# SCH_Cansat_PCB_Flight_Computer_Only_2026.net
KiCad netlist of a schematic drawn in EasyEDA
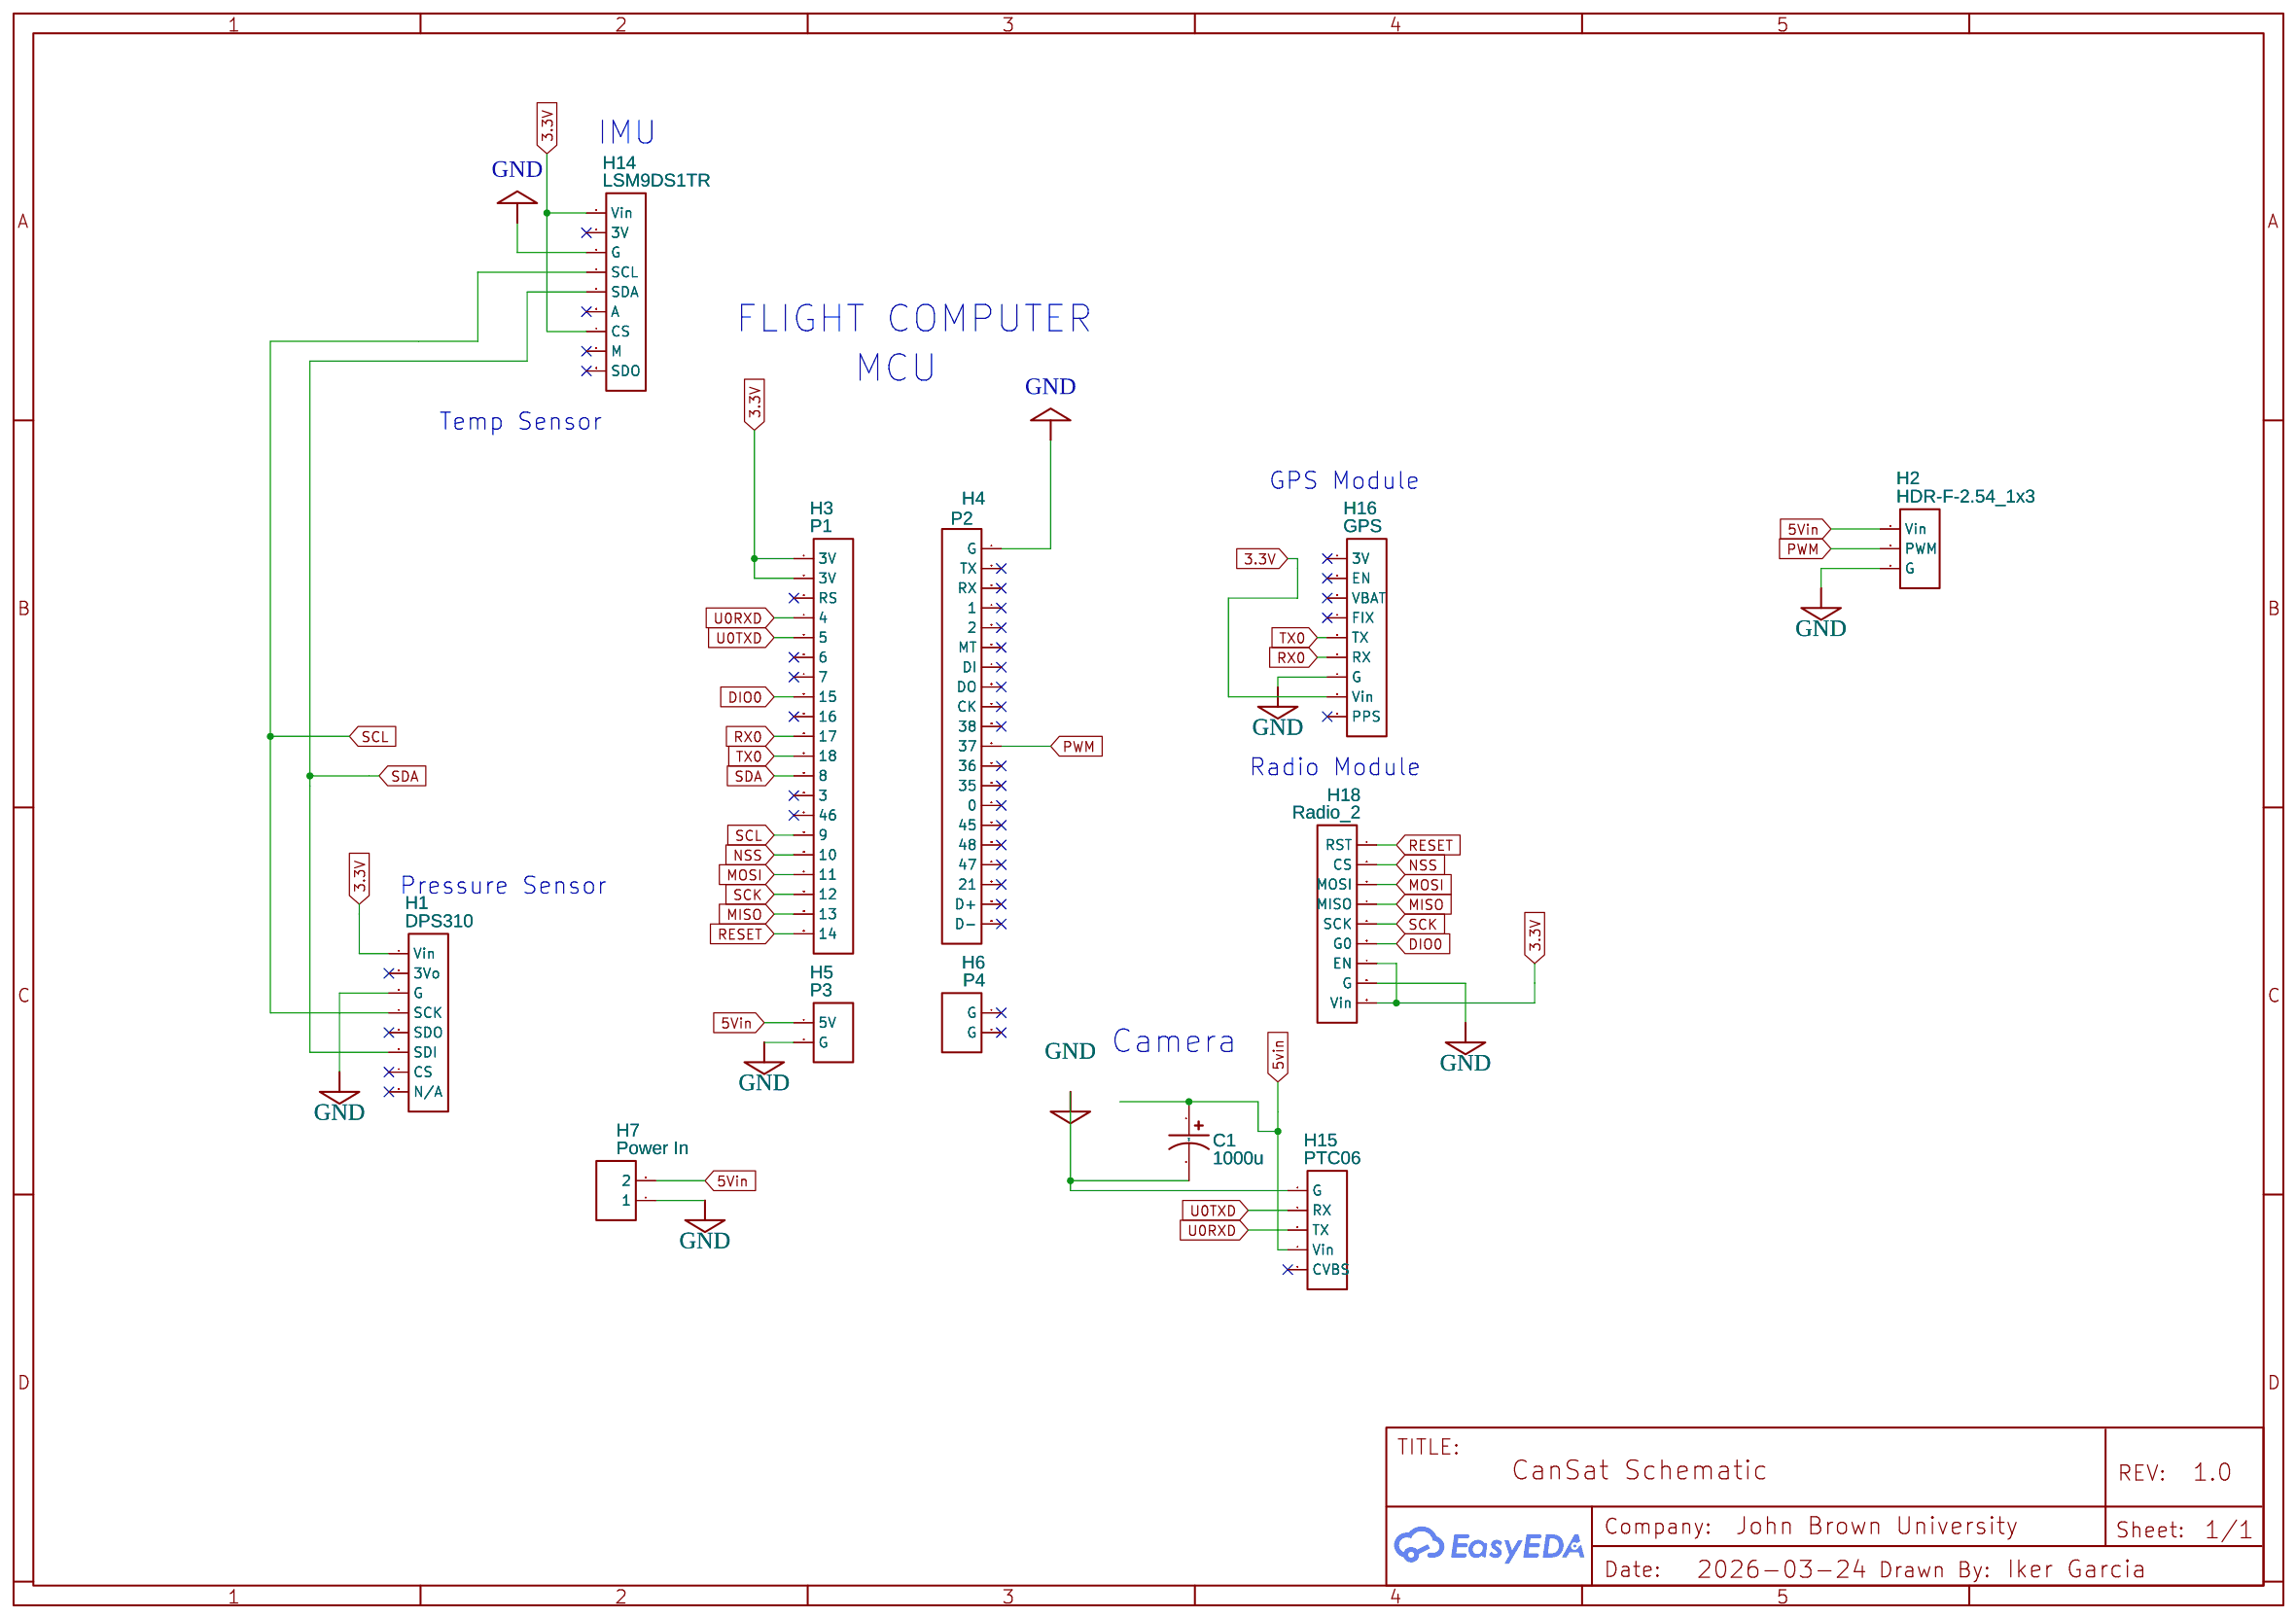
[diagram p0: schematic sheet]

(export (version "E")
  (design (tool "Eeschema 10.0.6"))
  (components
    (comp (ref "C1") (value "1000u") (libsource (lib "") (part "CE_TH_D6.3×F2.5_US")))
    (comp (ref "H1") (value "DPS310") (libsource (lib "") (part "HDR-F-2.54_1x8")))
    (comp (ref "H2") (value "HDR-F-2.54_1x3") (libsource (lib "") (part "HDR-F-2.54_1x3")))
    (comp (ref "H3") (value "P1") (libsource (lib "") (part "HDR-F-2.54_1x20")))
    (comp (ref "H4") (value "P2") (libsource (lib "") (part "HDR-F-2.54_1x20_1")))
    (comp (ref "H5") (value "P3") (libsource (lib "") (part "HDR-F-2.54_1x2_1")))
    (comp (ref "H6") (value "P4") (libsource (lib "") (part "HDR-F-2.54_1x2")))
    (comp (ref "H7") (value "Power In") (libsource (lib "") (part "HDR-F-2.54_1x2_2")))
    (comp (ref "H14") (value "LSM9DS1TR") (libsource (lib "") (part "HDR-F-2.54_1x9_2")))
    (comp (ref "H15") (value "PTC06") (libsource (lib "") (part "HDR-F-2.54_1x5")))
    (comp (ref "H16") (value "GPS") (libsource (lib "") (part "HDR-F-2.54_1x9_1")))
    (comp (ref "H18") (value "Radio_2") (libsource (lib "") (part "HDR-F-2.54_1x9")))
  )
  (nets
    (net (code "1") (name "3.3V") (class "Default")
      (node (ref "H1") (pin "1") (pinfunction "Vin_1") (pintype "unspecified"))
      (node (ref "H14") (pin "1") (pinfunction "Vin_1") (pintype "unspecified"))
      (node (ref "H14") (pin "7") (pinfunction "CS_7") (pintype "unspecified"))
      (node (ref "H16") (pin "8") (pinfunction "Vin_8") (pintype "unspecified"))
      (node (ref "H18") (pin "7") (pinfunction "EN_7") (pintype "unspecified"))
      (node (ref "H18") (pin "9") (pinfunction "Vin_9") (pintype "unspecified"))
      (node (ref "H3") (pin "1") (pinfunction "3V_1") (pintype "unspecified"))
      (node (ref "H3") (pin "2") (pinfunction "3V_2") (pintype "unspecified"))
    )
    (net (code "2") (name "5Vin") (class "Default")
      (node (ref "H2") (pin "1") (pinfunction "Vin_1") (pintype "input"))
      (node (ref "H5") (pin "1") (pinfunction "5V_1") (pintype "input"))
      (node (ref "H7") (pin "2") (pinfunction "2_2") (pintype "input"))
    )
    (net (code "3") (name "5vin") (class "Default")
      (node (ref "C1") (pin "1") (pinfunction "1_1") (pintype "unspecified"))
      (node (ref "H15") (pin "4") (pinfunction "Vin_4") (pintype "unspecified"))
    )
    (net (code "4") (name "DIO0") (class "Default")
      (node (ref "H18") (pin "6") (pinfunction "G0_6") (pintype "unspecified"))
      (node (ref "H3") (pin "8") (pinfunction "15_8") (pintype "unspecified"))
    )
    (net (code "5") (name "GND") (class "Default")
      (node (ref "C1") (pin "2") (pinfunction "2_2") (pintype "unspecified"))
      (node (ref "H1") (pin "3") (pinfunction "G_3") (pintype "unspecified"))
      (node (ref "H14") (pin "3") (pinfunction "G_3") (pintype "unspecified"))
      (node (ref "H15") (pin "1") (pinfunction "G_1") (pintype "unspecified"))
      (node (ref "H16") (pin "7") (pinfunction "G_7") (pintype "unspecified"))
      (node (ref "H18") (pin "8") (pinfunction "G_8") (pintype "unspecified"))
      (node (ref "H2") (pin "3") (pinfunction "G_3") (pintype "input"))
      (node (ref "H4") (pin "1") (pinfunction "G_1") (pintype "unspecified"))
      (node (ref "H5") (pin "2") (pinfunction "G_2") (pintype "input"))
      (node (ref "H7") (pin "1") (pinfunction "1_1") (pintype "input"))
    )
    (net (code "6") (name "MISO") (class "Default")
      (node (ref "H18") (pin "4") (pinfunction "MISO_4") (pintype "unspecified"))
      (node (ref "H3") (pin "19") (pinfunction "13_19") (pintype "unspecified"))
    )
    (net (code "7") (name "MOSI") (class "Default")
      (node (ref "H18") (pin "3") (pinfunction "MOSI_3") (pintype "unspecified"))
      (node (ref "H3") (pin "17") (pinfunction "11_17") (pintype "unspecified"))
    )
    (net (code "8") (name "NSS") (class "Default")
      (node (ref "H18") (pin "2") (pinfunction "CS_2") (pintype "unspecified"))
      (node (ref "H3") (pin "16") (pinfunction "10_16") (pintype "unspecified"))
    )
    (net (code "9") (name "PWM") (class "Default")
      (node (ref "H2") (pin "2") (pinfunction "PWM_2") (pintype "input"))
      (node (ref "H4") (pin "11") (pinfunction "37_11") (pintype "unspecified"))
    )
    (net (code "10") (name "RESET") (class "Default")
      (node (ref "H18") (pin "1") (pinfunction "RST_1") (pintype "unspecified"))
      (node (ref "H3") (pin "20") (pinfunction "14_20") (pintype "unspecified"))
    )
    (net (code "11") (name "RX0") (class "Default")
      (node (ref "H16") (pin "6") (pinfunction "RX_6") (pintype "unspecified"))
      (node (ref "H3") (pin "10") (pinfunction "17_10") (pintype "unspecified"))
    )
    (net (code "12") (name "SCK") (class "Default")
      (node (ref "H18") (pin "5") (pinfunction "SCK_5") (pintype "unspecified"))
      (node (ref "H3") (pin "18") (pinfunction "12_18") (pintype "unspecified"))
    )
    (net (code "13") (name "SCL") (class "Default")
      (node (ref "H1") (pin "4") (pinfunction "SCK_4") (pintype "unspecified"))
      (node (ref "H14") (pin "4") (pinfunction "SCL_4") (pintype "unspecified"))
      (node (ref "H3") (pin "15") (pinfunction "9_15") (pintype "unspecified"))
    )
    (net (code "14") (name "SDA") (class "Default")
      (node (ref "H1") (pin "6") (pinfunction "SDI_6") (pintype "unspecified"))
      (node (ref "H14") (pin "5") (pinfunction "SDA_5") (pintype "unspecified"))
      (node (ref "H3") (pin "12") (pinfunction "8_12") (pintype "unspecified"))
    )
    (net (code "15") (name "TX0") (class "Default")
      (node (ref "H16") (pin "5") (pinfunction "TX_5") (pintype "unspecified"))
      (node (ref "H3") (pin "11") (pinfunction "18_11") (pintype "unspecified"))
    )
    (net (code "16") (name "U0RXD") (class "Default")
      (node (ref "H15") (pin "3") (pinfunction "TX_3") (pintype "unspecified"))
      (node (ref "H3") (pin "4") (pinfunction "4_4") (pintype "unspecified"))
    )
    (net (code "17") (name "U0TXD") (class "Default")
      (node (ref "H15") (pin "2") (pinfunction "RX_2") (pintype "unspecified"))
      (node (ref "H3") (pin "5") (pinfunction "5_5") (pintype "unspecified"))
    )
    (net (code "18") (name "unconnected-(H1-3Vo-Pad2)") (class "Default")
      (node (ref "H1") (pin "2") (pinfunction "3Vo_2") (pintype "unspecified+no_connect"))
    )
    (net (code "19") (name "unconnected-(H1-CS-Pad7)") (class "Default")
      (node (ref "H1") (pin "7") (pinfunction "CS_7") (pintype "unspecified+no_connect"))
    )
    (net (code "20") (name "unconnected-(H1-N{slash}A-Pad8)") (class "Default")
      (node (ref "H1") (pin "8") (pinfunction "N/A_8") (pintype "unspecified+no_connect"))
    )
    (net (code "21") (name "unconnected-(H1-SDO-Pad5)") (class "Default")
      (node (ref "H1") (pin "5") (pinfunction "SDO_5") (pintype "unspecified+no_connect"))
    )
    (net (code "22") (name "unconnected-(H3-3-Pad13)") (class "Default")
      (node (ref "H3") (pin "13") (pinfunction "3_13") (pintype "unspecified+no_connect"))
    )
    (net (code "23") (name "unconnected-(H3-16-Pad9)") (class "Default")
      (node (ref "H3") (pin "9") (pinfunction "16_9") (pintype "unspecified+no_connect"))
    )
    (net (code "24") (name "unconnected-(H3-46-Pad14)") (class "Default")
      (node (ref "H3") (pin "14") (pinfunction "46_14") (pintype "unspecified+no_connect"))
    )
    (net (code "25") (name "unconnected-(H3-Pad6)") (class "Default")
      (node (ref "H3") (pin "6") (pinfunction "6_6") (pintype "unspecified+no_connect"))
    )
    (net (code "26") (name "unconnected-(H3-Pad7)") (class "Default")
      (node (ref "H3") (pin "7") (pinfunction "7_7") (pintype "unspecified+no_connect"))
    )
    (net (code "27") (name "unconnected-(H3-RS-Pad3)") (class "Default")
      (node (ref "H3") (pin "3") (pinfunction "RS_3") (pintype "unspecified+no_connect"))
    )
    (net (code "28") (name "unconnected-(H4-0-Pad14)") (class "Default")
      (node (ref "H4") (pin "14") (pinfunction "0_14") (pintype "unspecified+no_connect"))
    )
    (net (code "29") (name "unconnected-(H4-1-Pad4)") (class "Default")
      (node (ref "H4") (pin "4") (pinfunction "1_4") (pintype "unspecified+no_connect"))
    )
    (net (code "30") (name "unconnected-(H4-2-Pad5)") (class "Default")
      (node (ref "H4") (pin "5") (pinfunction "2_5") (pintype "unspecified+no_connect"))
    )
    (net (code "31") (name "unconnected-(H4-21-Pad18)") (class "Default")
      (node (ref "H4") (pin "18") (pinfunction "21_18") (pintype "unspecified+no_connect"))
    )
    (net (code "32") (name "unconnected-(H4-35-Pad13)") (class "Default")
      (node (ref "H4") (pin "13") (pinfunction "35_13") (pintype "unspecified+no_connect"))
    )
    (net (code "33") (name "unconnected-(H4-36-Pad12)") (class "Default")
      (node (ref "H4") (pin "12") (pinfunction "36_12") (pintype "unspecified+no_connect"))
    )
    (net (code "34") (name "unconnected-(H4-38-Pad10)") (class "Default")
      (node (ref "H4") (pin "10") (pinfunction "38_10") (pintype "unspecified+no_connect"))
    )
    (net (code "35") (name "unconnected-(H4-45-Pad15)") (class "Default")
      (node (ref "H4") (pin "15") (pinfunction "45_15") (pintype "unspecified+no_connect"))
    )
    (net (code "36") (name "unconnected-(H4-47-Pad17)") (class "Default")
      (node (ref "H4") (pin "17") (pinfunction "47_17") (pintype "unspecified+no_connect"))
    )
    (net (code "37") (name "unconnected-(H4-48-Pad16)") (class "Default")
      (node (ref "H4") (pin "16") (pinfunction "48_16") (pintype "unspecified+no_connect"))
    )
    (net (code "38") (name "unconnected-(H4-CK-Pad9)") (class "Default")
      (node (ref "H4") (pin "9") (pinfunction "CK_9") (pintype "unspecified+no_connect"))
    )
    (net (code "39") (name "unconnected-(H4-D+-Pad19)") (class "Default")
      (node (ref "H4") (pin "19") (pinfunction "D+_19") (pintype "unspecified+no_connect"))
    )
    (net (code "40") (name "unconnected-(H4-D--Pad20)") (class "Default")
      (node (ref "H4") (pin "20") (pinfunction "D-_20") (pintype "unspecified+no_connect"))
    )
    (net (code "41") (name "unconnected-(H4-DI-Pad7)") (class "Default")
      (node (ref "H4") (pin "7") (pinfunction "DI_7") (pintype "unspecified+no_connect"))
    )
    (net (code "42") (name "unconnected-(H4-DO-Pad8)") (class "Default")
      (node (ref "H4") (pin "8") (pinfunction "DO_8") (pintype "unspecified+no_connect"))
    )
    (net (code "43") (name "unconnected-(H4-MT-Pad6)") (class "Default")
      (node (ref "H4") (pin "6") (pinfunction "MT_6") (pintype "unspecified+no_connect"))
    )
    (net (code "44") (name "unconnected-(H4-RX-Pad3)") (class "Default")
      (node (ref "H4") (pin "3") (pinfunction "RX_3") (pintype "unspecified+no_connect"))
    )
    (net (code "45") (name "unconnected-(H4-TX-Pad2)") (class "Default")
      (node (ref "H4") (pin "2") (pinfunction "TX_2") (pintype "unspecified+no_connect"))
    )
    (net (code "46") (name "unconnected-(H6-G-Pad1)") (class "Default")
      (node (ref "H6") (pin "1") (pinfunction "G_1") (pintype "input+no_connect"))
    )
    (net (code "47") (name "unconnected-(H6-G-Pad2)") (class "Default")
      (node (ref "H6") (pin "2") (pinfunction "G_2") (pintype "input+no_connect"))
    )
    (net (code "48") (name "unconnected-(H14-3V-Pad2)") (class "Default")
      (node (ref "H14") (pin "2") (pinfunction "3V_2") (pintype "unspecified+no_connect"))
    )
    (net (code "49") (name "unconnected-(H14-A-Pad6)") (class "Default")
      (node (ref "H14") (pin "6") (pinfunction "A_6") (pintype "unspecified+no_connect"))
    )
    (net (code "50") (name "unconnected-(H14-M-Pad8)") (class "Default")
      (node (ref "H14") (pin "8") (pinfunction "M_8") (pintype "unspecified+no_connect"))
    )
    (net (code "51") (name "unconnected-(H14-SDO-Pad9)") (class "Default")
      (node (ref "H14") (pin "9") (pinfunction "SDO_9") (pintype "unspecified+no_connect"))
    )
    (net (code "52") (name "unconnected-(H15-CVBS-Pad5)") (class "Default")
      (node (ref "H15") (pin "5") (pinfunction "CVBS_5") (pintype "unspecified+no_connect"))
    )
    (net (code "53") (name "unconnected-(H16-3V-Pad1)") (class "Default")
      (node (ref "H16") (pin "1") (pinfunction "3V_1") (pintype "unspecified+no_connect"))
    )
    (net (code "54") (name "unconnected-(H16-EN-Pad2)") (class "Default")
      (node (ref "H16") (pin "2") (pinfunction "EN_2") (pintype "unspecified+no_connect"))
    )
    (net (code "55") (name "unconnected-(H16-FIX-Pad4)") (class "Default")
      (node (ref "H16") (pin "4") (pinfunction "FIX_4") (pintype "unspecified+no_connect"))
    )
    (net (code "56") (name "unconnected-(H16-PPS-Pad9)") (class "Default")
      (node (ref "H16") (pin "9") (pinfunction "PPS_9") (pintype "unspecified+no_connect"))
    )
    (net (code "57") (name "unconnected-(H16-VBAT-Pad3)") (class "Default")
      (node (ref "H16") (pin "3") (pinfunction "VBAT_3") (pintype "unspecified+no_connect"))
    )
  )
)
